# OBI_SlaveBoard_rev5.net
KiCad netlist of a schematic drawn in EAGLE
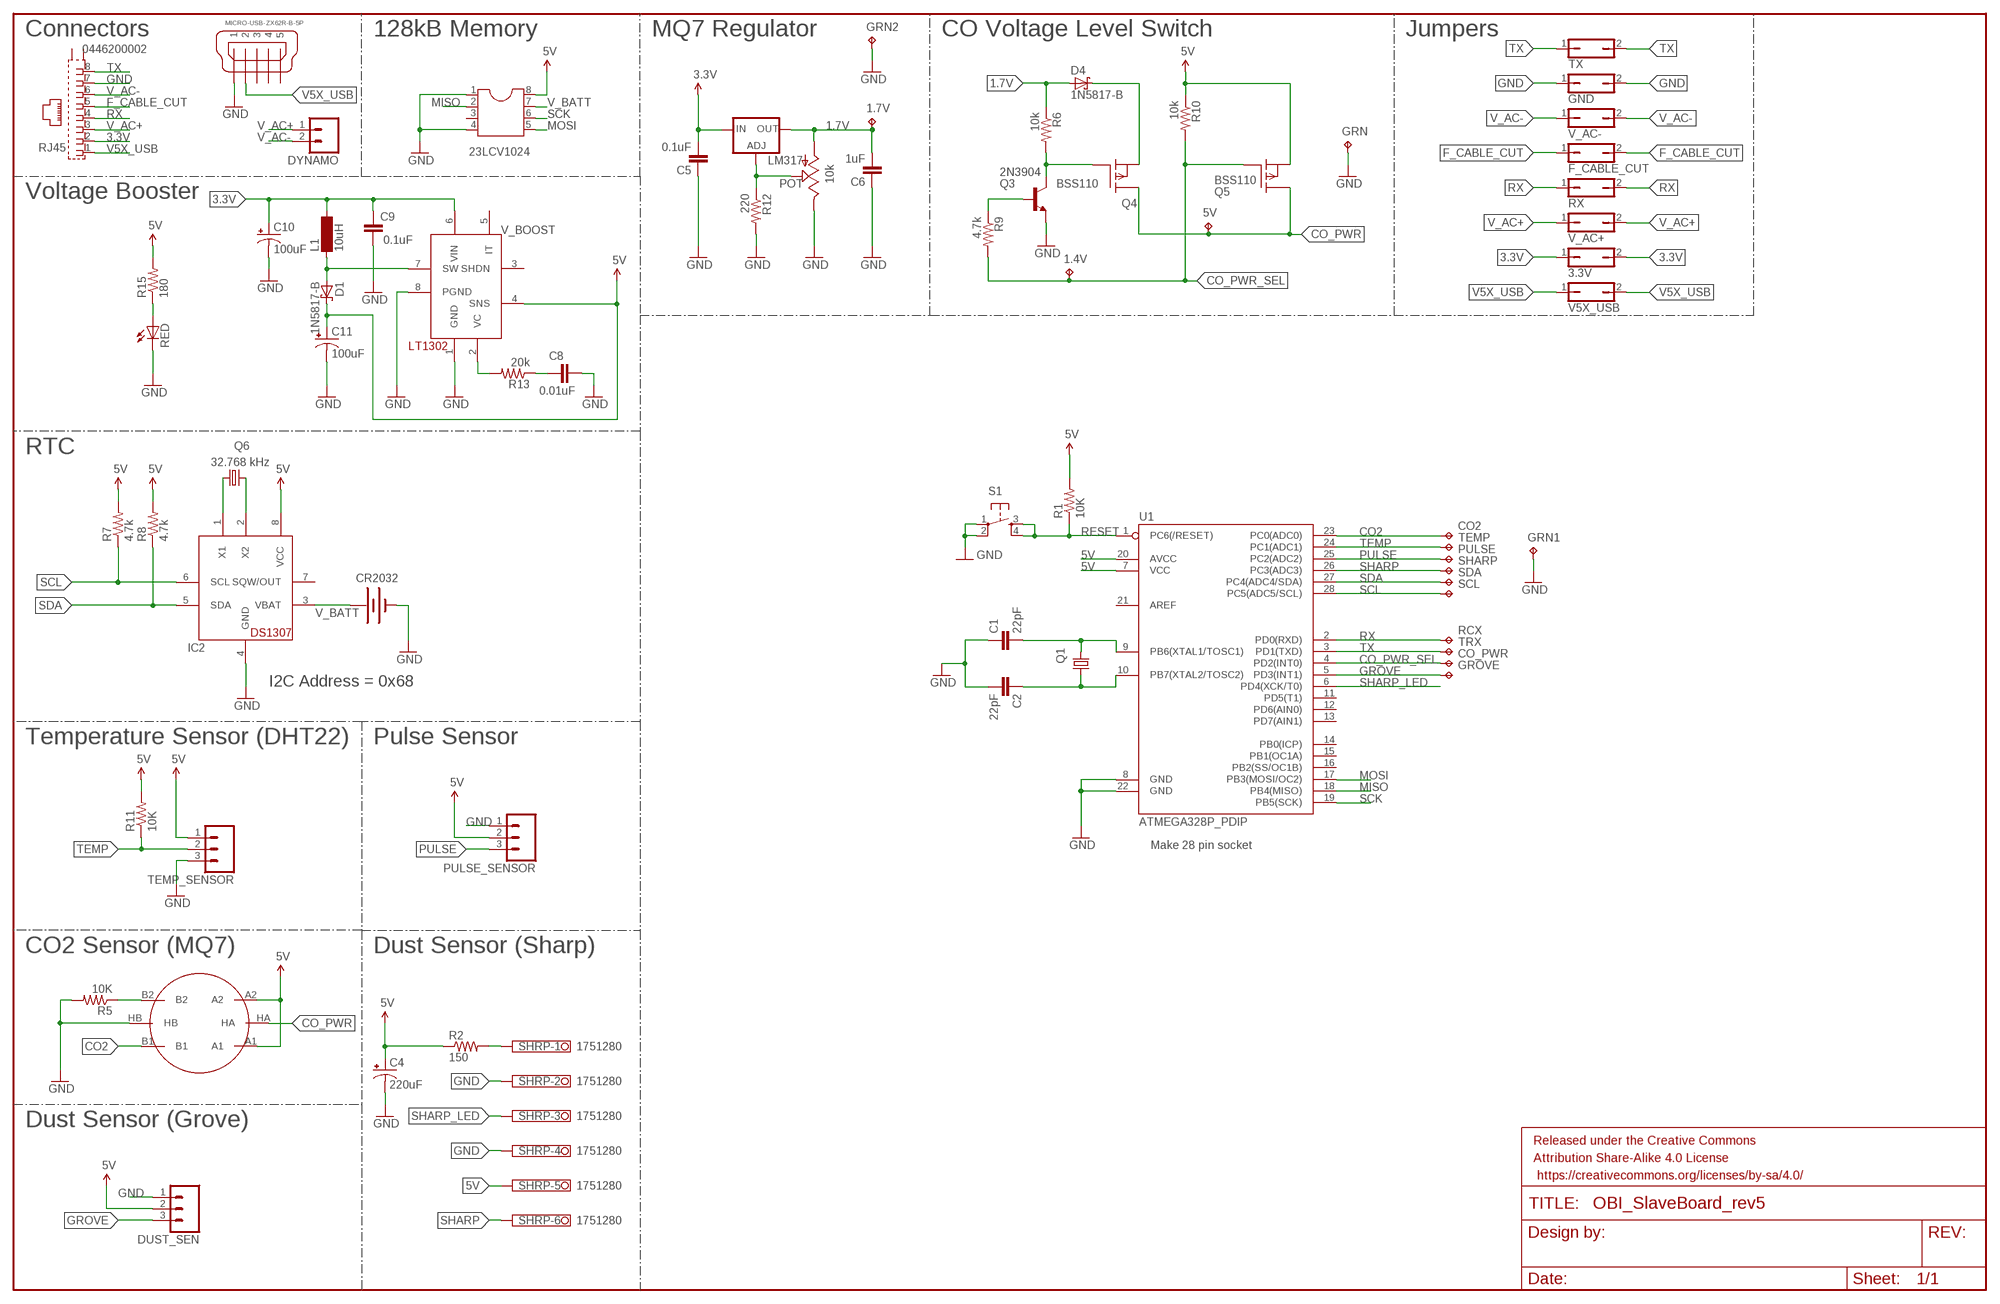
[diagram p0: schematic, sheet 1]

(export (version "E")
  (design (tool "Eeschema 10.0.6"))
  (components
    (comp (ref "1.4V")
      (value "TPPAD1-13")
      (footprint "eagle-import:P1-13")
      (libsource (lib "eagle-import") (part "TPPAD1-13"))
    )
    (comp (ref "1.7V")
      (value "TPPAD1-13")
      (footprint "eagle-import:P1-13")
      (libsource (lib "eagle-import") (part "TPPAD1-13"))
    )
    (comp (ref "3.3V")
      (value "JP1Q")
      (footprint "eagle-import:JP1")
      (libsource (lib "eagle-import") (part "JP1Q"))
    )
    (comp (ref "5V")
      (value "TPPAD1-13")
      (footprint "eagle-import:P1-13")
      (libsource (lib "eagle-import") (part "TPPAD1-13"))
    )
    (comp (ref "23LCV1024")
      (value "DIL8S")
      (footprint "eagle-import:SOCKET-08")
      (libsource (lib "eagle-import") (part "DIL8S"))
    )
    (comp (ref "C1")
      (value "22pF")
      (footprint "eagle-import:CAP-PTH-SMALL-KIT")
      (libsource (lib "eagle-import") (part "CAPKIT"))
    )
    (comp (ref "C2")
      (value "22pF")
      (footprint "eagle-import:CAP-PTH-SMALL-KIT")
      (libsource (lib "eagle-import") (part "CAPKIT"))
    )
    (comp (ref "C4")
      (value "220uF")
      (footprint "eagle-import:CPOL-RADIAL-10UF-25V")
      (libsource (lib "eagle-import") (part "CAP_POLPTH2"))
    )
    (comp (ref "C5")
      (value "0.1uF")
      (footprint "eagle-import:CAP-PTH-SMALL-KIT")
      (libsource (lib "eagle-import") (part "CAPKIT"))
    )
    (comp (ref "C6")
      (value "1uF")
      (footprint "eagle-import:CAP-PTH-SMALL-KIT")
      (libsource (lib "eagle-import") (part "CAPKIT"))
    )
    (comp (ref "C8")
      (value "0.01uF")
      (footprint "eagle-import:CAP-PTH-SMALL-KIT")
      (libsource (lib "eagle-import") (part "CAPKIT"))
    )
    (comp (ref "C9")
      (value "0.1uF")
      (footprint "eagle-import:CAP-PTH-SMALL-KIT")
      (libsource (lib "eagle-import") (part "CAPKIT"))
    )
    (comp (ref "C10")
      (value "100uF")
      (footprint "eagle-import:TT2D5")
      (libsource (lib "eagle-import") (part "CPOL-USTT2D5"))
    )
    (comp (ref "C11")
      (value "100uF")
      (footprint "eagle-import:TT2D5")
      (libsource (lib "eagle-import") (part "CPOL-USTT2D5"))
    )
    (comp (ref "CO2")
      (value "TPPAD1-13")
      (footprint "eagle-import:P1-13")
      (libsource (lib "eagle-import") (part "TPPAD1-13"))
    )
    (comp (ref "CO2_SENSOR")
      (value "METHANE_SENSOR")
      (footprint "eagle-import:MQ-3")
      (libsource (lib "eagle-import") (part "METHANE_SENSOR"))
    )
    (comp (ref "CO_PWR")
      (value "TPPAD1-13")
      (footprint "eagle-import:P1-13")
      (libsource (lib "eagle-import") (part "TPPAD1-13"))
    )
    (comp (ref "CR2032")
      (value "BATTERY20PTH")
      (footprint "eagle-import:BATTCOM_20MM_PTH")
      (libsource (lib "eagle-import") (part "BATTERY20PTH"))
    )
    (comp (ref "D1")
      (value "1N5817-B")
      (footprint "eagle-import:DO41-10")
      (libsource (lib "eagle-import") (part "SCHOTTKY-DIODEDO41"))
    )
    (comp (ref "D4")
      (value "1N5817-B")
      (footprint "eagle-import:DO41-10")
      (libsource (lib "eagle-import") (part "SCHOTTKY-DIODEDO41"))
    )
    (comp (ref "DUST_SEN")
      (value "M03SCREW")
      (footprint "eagle-import:SCREWTERMINAL-3.5MM-3")
      (libsource (lib "eagle-import") (part "M03SCREW"))
    )
    (comp (ref "DYNAMO")
      (value "M023.5MM")
      (footprint "eagle-import:SCREWTERMINAL-3.5MM-2")
      (libsource (lib "eagle-import") (part "M023.5MM"))
    )
    (comp (ref "FRAME1")
      (value "FRAME-LEDGER")
      (footprint "eagle-import:CREATIVE_COMMONS")
      (libsource (lib "eagle-import") (part "FRAME-LEDGER"))
    )
    (comp (ref "F_CABLE_CUT")
      (value "JP1Q")
      (footprint "eagle-import:JP1")
      (libsource (lib "eagle-import") (part "JP1Q"))
    )
    (comp (ref "GND")
      (value "JP1Q")
      (footprint "eagle-import:JP1")
      (libsource (lib "eagle-import") (part "JP1Q"))
    )
    (comp (ref "GRN")
      (value "TPPAD1-13")
      (footprint "eagle-import:P1-13")
      (libsource (lib "eagle-import") (part "TPPAD1-13"))
    )
    (comp (ref "GRN1")
      (value "TPPAD1-13")
      (footprint "eagle-import:P1-13")
      (libsource (lib "eagle-import") (part "TPPAD1-13"))
    )
    (comp (ref "GRN2")
      (value "TPPAD1-13")
      (footprint "eagle-import:P1-13")
      (libsource (lib "eagle-import") (part "TPPAD1-13"))
    )
    (comp (ref "GROVE")
      (value "TPPAD1-13")
      (footprint "eagle-import:P1-13")
      (libsource (lib "eagle-import") (part "TPPAD1-13"))
    )
    (comp (ref "IC2")
      (value "DS1307")
      (footprint "eagle-import:DIL08")
      (libsource (lib "eagle-import") (part "DS1307"))
    )
    (comp (ref "L1")
      (value "10uH")
      (footprint "eagle-import:BS11")
      (libsource (lib "eagle-import") (part "BS11"))
    )
    (comp (ref "LM317")
      (value "LM317TS")
      (footprint "eagle-import:317TS")
      (libsource (lib "eagle-import") (part "LM317TS"))
    )
    (comp (ref "MICROB")
      (value "MICRO-USB-ZX62R-B-5P")
      (footprint "eagle-import:ZX62R-B-5P")
      (libsource (lib "eagle-import") (part "MICRO-USB-ZX62R-B-5P"))
    )
    (comp (ref "POT")
      (value "10k")
      (footprint "eagle-import:CT6")
      (libsource (lib "eagle-import") (part "TRIM_US-CT6"))
    )
    (comp (ref "PULSE")
      (value "TPPAD1-13")
      (footprint "eagle-import:P1-13")
      (libsource (lib "eagle-import") (part "TPPAD1-13"))
    )
    (comp (ref "PULSE_SENSOR")
      (value "M03SCREW")
      (footprint "eagle-import:SCREWTERMINAL-3.5MM-3")
      (libsource (lib "eagle-import") (part "M03SCREW"))
    )
    (comp (ref "Q1")
      (value "CRYSTALHC49S")
      (footprint "eagle-import:HC49_S")
      (libsource (lib "eagle-import") (part "CRYSTALHC49S"))
    )
    (comp (ref "Q3")
      (value "2N3904")
      (footprint "eagle-import:TO-92")
      (libsource (lib "eagle-import") (part "TRANSISTOR_NPN2N3904"))
    )
    (comp (ref "Q4")
      (value "BSS110")
      (footprint "eagle-import:TO92")
      (libsource (lib "eagle-import") (part "BSS110"))
    )
    (comp (ref "Q5")
      (value "BSS110")
      (footprint "eagle-import:TO92")
      (libsource (lib "eagle-import") (part "BSS110"))
    )
    (comp (ref "Q6")
      (value "32.768 kHz")
      (footprint "eagle-import:TC26V")
      (libsource (lib "eagle-import") (part "CRYSTALTC26V"))
    )
    (comp (ref "R1")
      (value "10K")
      (footprint "eagle-import:AXIAL-0.4")
      (libsource (lib "eagle-import") (part "RESISTORPTH-1/4W"))
    )
    (comp (ref "R2")
      (value "150")
      (footprint "eagle-import:AXIAL-0.4")
      (libsource (lib "eagle-import") (part "SparkFun-Resistors_RESISTORPTH-1/4W"))
    )
    (comp (ref "R5")
      (value "10K")
      (footprint "eagle-import:AXIAL-0.4")
      (libsource (lib "eagle-import") (part "RESISTORPTH-1/4W"))
    )
    (comp (ref "R6")
      (value "10k")
      (footprint "eagle-import:AXIAL-0.4")
      (libsource (lib "eagle-import") (part "SparkFun-Resistors_RESISTORPTH-1/4W"))
    )
    (comp (ref "R7")
      (value "4.7k")
      (footprint "eagle-import:AXIAL-0.4")
      (libsource (lib "eagle-import") (part "RESISTORPTH-1/4W"))
    )
    (comp (ref "R8")
      (value "4.7k")
      (footprint "eagle-import:AXIAL-0.4")
      (libsource (lib "eagle-import") (part "RESISTORPTH-1/4W"))
    )
    (comp (ref "R9")
      (value "4.7k")
      (footprint "eagle-import:AXIAL-0.4")
      (libsource (lib "eagle-import") (part "SparkFun-Resistors_RESISTORPTH-1/4W"))
    )
    (comp (ref "R10")
      (value "10k")
      (footprint "eagle-import:AXIAL-0.4")
      (libsource (lib "eagle-import") (part "SparkFun-Resistors_RESISTORPTH-1/4W"))
    )
    (comp (ref "R11")
      (value "10K")
      (footprint "eagle-import:AXIAL-0.4")
      (libsource (lib "eagle-import") (part "SparkFun-Resistors_RESISTORPTH-1/4W"))
    )
    (comp (ref "R12")
      (value "220")
      (footprint "eagle-import:AXIAL-0.4")
      (libsource (lib "eagle-import") (part "SparkFun-Resistors_RESISTORPTH-1/4W"))
    )
    (comp (ref "R13")
      (value "20k")
      (footprint "eagle-import:AXIAL-0.4")
      (libsource (lib "eagle-import") (part "SparkFun-Resistors_RESISTORPTH-1/4W"))
    )
    (comp (ref "R15")
      (value "180")
      (footprint "eagle-import:AXIAL-0.4")
      (libsource (lib "eagle-import") (part "RESISTORPTH-1/4W"))
    )
    (comp (ref "RCX")
      (value "TPPAD1-13")
      (footprint "eagle-import:P1-13")
      (libsource (lib "eagle-import") (part "TPPAD1-13"))
    )
    (comp (ref "RED")
      (value "LEDCHIPLED_1206")
      (footprint "eagle-import:CHIPLED_1206")
      (libsource (lib "eagle-import") (part "LEDCHIPLED_1206"))
    )
    (comp (ref "RJ45")
      (value "0446200002")
      (footprint "eagle-import:0446200002")
      (fields (field (name "MF") "MOLEX"))
      (libsource (lib "eagle-import") (part "0446200002"))
    )
    (comp (ref "RX")
      (value "JP1Q")
      (footprint "eagle-import:JP1")
      (libsource (lib "eagle-import") (part "JP1Q"))
    )
    (comp (ref "S1")
      (value "TAC_SWITCHPTH")
      (footprint "eagle-import:TACTILE-PTH")
      (libsource (lib "eagle-import") (part "TAC_SWITCHPTH"))
    )
    (comp (ref "SCL")
      (value "TPPAD1-13")
      (footprint "eagle-import:P1-13")
      (libsource (lib "eagle-import") (part "TPPAD1-13"))
    )
    (comp (ref "SDA")
      (value "TPPAD1-13")
      (footprint "eagle-import:P1-13")
      (libsource (lib "eagle-import") (part "TPPAD1-13"))
    )
    (comp (ref "SHARP")
      (value "TPPAD1-13")
      (footprint "eagle-import:P1-13")
      (libsource (lib "eagle-import") (part "TPPAD1-13"))
    )
    (comp (ref "SHRP")
      (value "1751280")
      (footprint "eagle-import:1751280")
      (libsource (lib "eagle-import") (part "1751280"))
    )
    (comp (ref "TEMP")
      (value "TPPAD1-13")
      (footprint "eagle-import:P1-13")
      (libsource (lib "eagle-import") (part "TPPAD1-13"))
    )
    (comp (ref "TEMP_SENSOR")
      (value "M03SCREW")
      (footprint "eagle-import:SCREWTERMINAL-3.5MM-3")
      (libsource (lib "eagle-import") (part "M03SCREW"))
    )
    (comp (ref "TRX")
      (value "TPPAD1-13")
      (footprint "eagle-import:P1-13")
      (libsource (lib "eagle-import") (part "TPPAD1-13"))
    )
    (comp (ref "TX")
      (value "JP1Q")
      (footprint "eagle-import:JP1")
      (libsource (lib "eagle-import") (part "JP1Q"))
    )
    (comp (ref "U1")
      (value "ATMEGA328P_PDIP")
      (footprint "eagle-import:DIL28-3")
      (libsource (lib "eagle-import") (part "ATMEGA328P_PDIP"))
    )
    (comp (ref "V5X_USB")
      (value "JP1Q")
      (footprint "eagle-import:JP1")
      (libsource (lib "eagle-import") (part "JP1Q"))
    )
    (comp (ref "V_AC+")
      (value "JP1Q")
      (footprint "eagle-import:JP1")
      (libsource (lib "eagle-import") (part "JP1Q"))
    )
    (comp (ref "V_AC-")
      (value "JP1Q")
      (footprint "eagle-import:JP1")
      (libsource (lib "eagle-import") (part "JP1Q"))
    )
    (comp (ref "V_BOOST")
      (value "LT1302")
      (footprint "eagle-import:DIL08")
      (libsource (lib "eagle-import") (part "LT1302"))
    )
  )
  (nets
    (net (code "1") (name "/MISO") (class "Default")
      (node (ref "23LCV1024") (pin "2") (pinfunction "2_2") (pintype "passive"))
      (node (ref "U1") (pin "18") (pinfunction "PB4(MISO)_18") (pintype "bidirectional"))
    )
    (net (code "2") (name "/MOSI") (class "Default")
      (node (ref "23LCV1024") (pin "5") (pinfunction "5_5") (pintype "passive"))
      (node (ref "U1") (pin "17") (pinfunction "PB3(MOSI/OC2)_17") (pintype "bidirectional"))
    )
    (net (code "3") (name "/RESET") (class "Default")
      (node (ref "R1") (pin "P$1") (pinfunction "1_P$1") (pintype "passive"))
      (node (ref "S1") (pin "3") (pinfunction "3_3") (pintype "passive"))
      (node (ref "S1") (pin "4") (pinfunction "4_4") (pintype "passive"))
      (node (ref "U1") (pin "1") (pinfunction "PC6(/RESET)_1") (pintype "bidirectional"))
    )
    (net (code "4") (name "/SCK") (class "Default")
      (node (ref "23LCV1024") (pin "6") (pinfunction "6_6") (pintype "passive"))
      (node (ref "U1") (pin "19") (pinfunction "PB5(SCK)_19") (pintype "bidirectional"))
    )
    (net (code "5") (name "/V_BATT") (class "Default")
      (node (ref "23LCV1024") (pin "7") (pinfunction "7_7") (pintype "passive"))
      (node (ref "CR2032") (pin "1") (pinfunction "+_1") (pintype "power_in"))
      (node (ref "IC2") (pin "3") (pinfunction "VBAT_3") (pintype "power_in"))
    )
    (net (code "6") (name "1.7V") (class "Default")
      (node (ref "1.7V") (pin "TP") (pinfunction "TP_TP") (pintype "input"))
      (node (ref "C6") (pin "2") (pinfunction "2_2") (pintype "passive"))
      (node (ref "D4") (pin "A") (pinfunction "A_A") (pintype "passive"))
      (node (ref "LM317") (pin "2") (pinfunction "OUT_2") (pintype "passive"))
      (node (ref "POT") (pin "A") (pinfunction "A_A") (pintype "passive"))
      (node (ref "R6") (pin "P$1") (pinfunction "1_P$1") (pintype "passive"))
    )
    (net (code "7") (name "3.3V") (class "Default")
      (node (ref "3.3V") (pin "1") (pinfunction "1_1") (pintype "passive"))
      (node (ref "3.3V") (pin "2") (pinfunction "2_2") (pintype "passive"))
      (node (ref "C10") (pin "+") (pinfunction "+_+") (pintype "passive"))
      (node (ref "C5") (pin "2") (pinfunction "2_2") (pintype "passive"))
      (node (ref "C9") (pin "1") (pinfunction "1_1") (pintype "passive"))
      (node (ref "L1") (pin "2") (pinfunction "2_2") (pintype "passive"))
      (node (ref "LM317") (pin "3") (pinfunction "IN_3") (pintype "input"))
      (node (ref "RJ45") (pin "2") (pinfunction "2_2") (pintype "passive"))
      (node (ref "V_BOOST") (pin "6") (pinfunction "VIN_6") (pintype "input"))
    )
    (net (code "8") (name "5V") (class "Default")
      (node (ref "23LCV1024") (pin "8") (pinfunction "8_8") (pintype "passive"))
      (node (ref "C11") (pin "+") (pinfunction "+_+") (pintype "passive"))
      (node (ref "C4") (pin "1") (pinfunction "+_1") (pintype "passive"))
      (node (ref "CO2_SENSOR") (pin "A1") (pinfunction "A1_A1") (pintype "bidirectional"))
      (node (ref "CO2_SENSOR") (pin "A2") (pinfunction "A2_A2") (pintype "bidirectional"))
      (node (ref "D1") (pin "C") (pinfunction "C_C") (pintype "passive"))
      (node (ref "DUST_SEN") (pin "2") (pinfunction "2_2") (pintype "passive"))
      (node (ref "IC2") (pin "8") (pinfunction "VCC_8") (pintype "power_in"))
      (node (ref "PULSE_SENSOR") (pin "2") (pinfunction "2_2") (pintype "passive"))
      (node (ref "Q5") (pin "1") (pinfunction "S_1") (pintype "passive"))
      (node (ref "R1") (pin "P$2") (pinfunction "2_P$2") (pintype "passive"))
      (node (ref "R10") (pin "P$1") (pinfunction "1_P$1") (pintype "passive"))
      (node (ref "R11") (pin "P$2") (pinfunction "2_P$2") (pintype "passive"))
      (node (ref "R15") (pin "P$2") (pinfunction "2_P$2") (pintype "passive"))
      (node (ref "R2") (pin "P$1") (pinfunction "1_P$1") (pintype "passive"))
      (node (ref "R7") (pin "P$2") (pinfunction "2_P$2") (pintype "passive"))
      (node (ref "R8") (pin "P$2") (pinfunction "2_P$2") (pintype "passive"))
      (node (ref "SHRP") (pin "5") (pinfunction "K_5") (pintype "passive"))
      (node (ref "TEMP_SENSOR") (pin "1") (pinfunction "1_1") (pintype "passive"))
      (node (ref "U1") (pin "20") (pinfunction "AVCC_20") (pintype "bidirectional"))
      (node (ref "U1") (pin "7") (pinfunction "VCC_7") (pintype "bidirectional"))
      (node (ref "V_BOOST") (pin "4") (pinfunction "SNS_4") (pintype "passive"))
    )
    (net (code "9") (name "CO2") (class "Default")
      (node (ref "CO2") (pin "TP") (pinfunction "TP_TP") (pintype "input"))
      (node (ref "CO2_SENSOR") (pin "B1") (pinfunction "B1_B1") (pintype "bidirectional"))
      (node (ref "U1") (pin "23") (pinfunction "PC0(ADC0)_23") (pintype "bidirectional"))
    )
    (net (code "10") (name "CO_PWR") (class "Default")
      (node (ref "5V") (pin "TP") (pinfunction "TP_TP") (pintype "input"))
      (node (ref "CO2_SENSOR") (pin "HA") (pinfunction "HA_HA") (pintype "bidirectional"))
      (node (ref "Q4") (pin "3") (pinfunction "D_3") (pintype "passive"))
      (node (ref "Q5") (pin "3") (pinfunction "D_3") (pintype "passive"))
    )
    (net (code "11") (name "CO_PWR_SEL") (class "Default")
      (node (ref "1.4V") (pin "TP") (pinfunction "TP_TP") (pintype "input"))
      (node (ref "CO_PWR") (pin "TP") (pinfunction "TP_TP") (pintype "input"))
      (node (ref "Q5") (pin "2") (pinfunction "G_2") (pintype "passive"))
      (node (ref "R10") (pin "P$2") (pinfunction "2_P$2") (pintype "passive"))
      (node (ref "R9") (pin "P$2") (pinfunction "2_P$2") (pintype "passive"))
      (node (ref "U1") (pin "4") (pinfunction "PD2(INT0)_4") (pintype "bidirectional"))
    )
    (net (code "12") (name "F_CABLE_CUT") (class "Default")
      (node (ref "F_CABLE_CUT") (pin "1") (pinfunction "1_1") (pintype "passive"))
      (node (ref "F_CABLE_CUT") (pin "2") (pinfunction "2_2") (pintype "passive"))
      (node (ref "RJ45") (pin "5") (pinfunction "5_5") (pintype "passive"))
    )
    (net (code "13") (name "GND") (class "Default")
      (node (ref "23LCV1024") (pin "1") (pinfunction "1_1") (pintype "passive"))
      (node (ref "23LCV1024") (pin "4") (pinfunction "4_4") (pintype "passive"))
      (node (ref "C1") (pin "1") (pinfunction "1_1") (pintype "passive"))
      (node (ref "C10") (pin "-") (pinfunction "-_-") (pintype "passive"))
      (node (ref "C11") (pin "-") (pinfunction "-_-") (pintype "passive"))
      (node (ref "C2") (pin "2") (pinfunction "2_2") (pintype "passive"))
      (node (ref "C4") (pin "2") (pinfunction "-_2") (pintype "passive"))
      (node (ref "C5") (pin "1") (pinfunction "1_1") (pintype "passive"))
      (node (ref "C6") (pin "1") (pinfunction "1_1") (pintype "passive"))
      (node (ref "C8") (pin "1") (pinfunction "1_1") (pintype "passive"))
      (node (ref "C9") (pin "2") (pinfunction "2_2") (pintype "passive"))
      (node (ref "CO2_SENSOR") (pin "HB") (pinfunction "HB_HB") (pintype "bidirectional"))
      (node (ref "CR2032") (pin "2") (pinfunction "-_2") (pintype "power_in"))
      (node (ref "DUST_SEN") (pin "1") (pinfunction "1_1") (pintype "passive"))
      (node (ref "GND") (pin "1") (pinfunction "1_1") (pintype "passive"))
      (node (ref "GND") (pin "2") (pinfunction "2_2") (pintype "passive"))
      (node (ref "GRN") (pin "TP") (pinfunction "TP_TP") (pintype "input"))
      (node (ref "GRN1") (pin "TP") (pinfunction "TP_TP") (pintype "input"))
      (node (ref "GRN2") (pin "TP") (pinfunction "TP_TP") (pintype "input"))
      (node (ref "IC2") (pin "4") (pinfunction "GND_4") (pintype "power_in"))
      (node (ref "MICROB") (pin "1") (pinfunction "1_1") (pintype "input"))
      (node (ref "POT") (pin "E") (pinfunction "E_E") (pintype "passive"))
      (node (ref "PULSE_SENSOR") (pin "1") (pinfunction "1_1") (pintype "passive"))
      (node (ref "Q3") (pin "1") (pinfunction "E_1") (pintype "passive"))
      (node (ref "R12") (pin "P$2") (pinfunction "2_P$2") (pintype "passive"))
      (node (ref "R5") (pin "P$2") (pinfunction "2_P$2") (pintype "passive"))
      (node (ref "RED") (pin "C") (pinfunction "C_C") (pintype "passive"))
      (node (ref "RJ45") (pin "7") (pinfunction "7_7") (pintype "passive"))
      (node (ref "S1") (pin "1") (pinfunction "1_1") (pintype "passive"))
      (node (ref "S1") (pin "2") (pinfunction "2_2") (pintype "passive"))
      (node (ref "SHRP") (pin "2") (pinfunction "K_2") (pintype "passive"))
      (node (ref "SHRP") (pin "4") (pinfunction "K_4") (pintype "passive"))
      (node (ref "TEMP_SENSOR") (pin "3") (pinfunction "3_3") (pintype "passive"))
      (node (ref "U1") (pin "22") (pinfunction "GND_22") (pintype "bidirectional"))
      (node (ref "U1") (pin "8") (pinfunction "GND_8") (pintype "bidirectional"))
      (node (ref "V_BOOST") (pin "1") (pinfunction "GND_1") (pintype "input"))
      (node (ref "V_BOOST") (pin "8") (pinfunction "PGND_8") (pintype "input"))
    )
    (net (code "14") (name "GROVE") (class "Default")
      (node (ref "DUST_SEN") (pin "3") (pinfunction "3_3") (pintype "passive"))
      (node (ref "GROVE") (pin "TP") (pinfunction "TP_TP") (pintype "input"))
      (node (ref "U1") (pin "5") (pinfunction "PD3(INT1)_5") (pintype "bidirectional"))
    )
    (net (code "15") (name "Net-(IC2-X1)") (class "Default")
      (node (ref "IC2") (pin "1") (pinfunction "X1_1") (pintype "passive"))
      (node (ref "Q6") (pin "1") (pinfunction "1_1") (pintype "passive"))
    )
    (net (code "16") (name "Net-(IC2-X2)") (class "Default")
      (node (ref "IC2") (pin "2") (pinfunction "X2_2") (pintype "passive"))
      (node (ref "Q6") (pin "2") (pinfunction "2_2") (pintype "passive"))
    )
    (net (code "17") (name "Net-(LM317-ADJ)") (class "Default")
      (node (ref "LM317") (pin "1") (pinfunction "ADJ_1") (pintype "input"))
      (node (ref "POT") (pin "S") (pinfunction "S_S") (pintype "passive"))
      (node (ref "R12") (pin "P$1") (pinfunction "1_P$1") (pintype "passive"))
    )
    (net (code "18") (name "Net-(Q3-B)") (class "Default")
      (node (ref "Q3") (pin "2") (pinfunction "B_2") (pintype "passive"))
      (node (ref "R9") (pin "P$1") (pinfunction "1_P$1") (pintype "passive"))
    )
    (net (code "19") (name "Net-(Q3-C)") (class "Default")
      (node (ref "Q3") (pin "3") (pinfunction "C_3") (pintype "passive"))
      (node (ref "Q4") (pin "2") (pinfunction "G_2") (pintype "passive"))
      (node (ref "R6") (pin "P$2") (pinfunction "2_P$2") (pintype "passive"))
    )
    (net (code "20") (name "Net-(Q4-S)") (class "Default")
      (node (ref "D4") (pin "C") (pinfunction "C_C") (pintype "passive"))
      (node (ref "Q4") (pin "1") (pinfunction "S_1") (pintype "passive"))
    )
    (net (code "21") (name "Net-(R2-2)") (class "Default")
      (node (ref "R2") (pin "P$2") (pinfunction "2_P$2") (pintype "passive"))
      (node (ref "SHRP") (pin "1") (pinfunction "K_1") (pintype "passive"))
    )
    (net (code "22") (name "Net-(R5-1)") (class "Default")
      (node (ref "CO2_SENSOR") (pin "B2") (pinfunction "B2_B2") (pintype "bidirectional"))
      (node (ref "R5") (pin "P$1") (pinfunction "1_P$1") (pintype "passive"))
    )
    (net (code "23") (name "Net-(R13-1)") (class "Default")
      (node (ref "C8") (pin "2") (pinfunction "2_2") (pintype "passive"))
      (node (ref "R13") (pin "P$1") (pinfunction "1_P$1") (pintype "passive"))
    )
    (net (code "24") (name "Net-(R13-2)") (class "Default")
      (node (ref "R13") (pin "P$2") (pinfunction "2_P$2") (pintype "passive"))
      (node (ref "V_BOOST") (pin "2") (pinfunction "VC_2") (pintype "passive"))
    )
    (net (code "25") (name "Net-(R15-1)") (class "Default")
      (node (ref "R15") (pin "P$1") (pinfunction "1_P$1") (pintype "passive"))
      (node (ref "RED") (pin "A") (pinfunction "A_A") (pintype "passive"))
    )
    (net (code "26") (name "Net-(U1-PB6(XTAL1{slash}TOSC1))") (class "Default")
      (node (ref "C1") (pin "2") (pinfunction "2_2") (pintype "passive"))
      (node (ref "Q1") (pin "2") (pinfunction "2_2") (pintype "passive"))
      (node (ref "U1") (pin "9") (pinfunction "PB6(XTAL1/TOSC1)_9") (pintype "bidirectional"))
    )
    (net (code "27") (name "Net-(U1-PB7(XTAL2{slash}TOSC2))") (class "Default")
      (node (ref "C2") (pin "1") (pinfunction "1_1") (pintype "passive"))
      (node (ref "Q1") (pin "1") (pinfunction "1_1") (pintype "passive"))
      (node (ref "U1") (pin "10") (pinfunction "PB7(XTAL2/TOSC2)_10") (pintype "bidirectional"))
    )
    (net (code "28") (name "Net-(V_BOOST-SW)") (class "Default")
      (node (ref "D1") (pin "A") (pinfunction "A_A") (pintype "passive"))
      (node (ref "L1") (pin "1") (pinfunction "1_1") (pintype "passive"))
      (node (ref "V_BOOST") (pin "7") (pinfunction "SW_7") (pintype "input"))
    )
    (net (code "29") (name "PULSE") (class "Default")
      (node (ref "PULSE") (pin "TP") (pinfunction "TP_TP") (pintype "input"))
      (node (ref "PULSE_SENSOR") (pin "3") (pinfunction "3_3") (pintype "passive"))
      (node (ref "U1") (pin "25") (pinfunction "PC2(ADC2)_25") (pintype "bidirectional"))
    )
    (net (code "30") (name "RX") (class "Default")
      (node (ref "RCX") (pin "TP") (pinfunction "TP_TP") (pintype "input"))
      (node (ref "RJ45") (pin "4") (pinfunction "4_4") (pintype "passive"))
      (node (ref "RX") (pin "1") (pinfunction "1_1") (pintype "passive"))
      (node (ref "RX") (pin "2") (pinfunction "2_2") (pintype "passive"))
      (node (ref "U1") (pin "2") (pinfunction "PD0(RXD)_2") (pintype "bidirectional"))
    )
    (net (code "31") (name "SCL") (class "Default")
      (node (ref "IC2") (pin "6") (pinfunction "SCL_6") (pintype "bidirectional"))
      (node (ref "R7") (pin "P$1") (pinfunction "1_P$1") (pintype "passive"))
      (node (ref "SCL") (pin "TP") (pinfunction "TP_TP") (pintype "input"))
      (node (ref "U1") (pin "28") (pinfunction "PC5(ADC5/SCL)_28") (pintype "bidirectional"))
    )
    (net (code "32") (name "SDA") (class "Default")
      (node (ref "IC2") (pin "5") (pinfunction "SDA_5") (pintype "bidirectional"))
      (node (ref "R8") (pin "P$1") (pinfunction "1_P$1") (pintype "passive"))
      (node (ref "SDA") (pin "TP") (pinfunction "TP_TP") (pintype "input"))
      (node (ref "U1") (pin "27") (pinfunction "PC4(ADC4/SDA)_27") (pintype "bidirectional"))
    )
    (net (code "33") (name "SHARP") (class "Default")
      (node (ref "SHARP") (pin "TP") (pinfunction "TP_TP") (pintype "input"))
      (node (ref "SHRP") (pin "6") (pinfunction "K_6") (pintype "passive"))
      (node (ref "U1") (pin "26") (pinfunction "PC3(ADC3)_26") (pintype "bidirectional"))
    )
    (net (code "34") (name "SHARP_LED") (class "Default")
      (node (ref "SHRP") (pin "3") (pinfunction "K_3") (pintype "passive"))
      (node (ref "U1") (pin "6") (pinfunction "PD4(XCK/T0)_6") (pintype "bidirectional"))
    )
    (net (code "35") (name "TEMP") (class "Default")
      (node (ref "R11") (pin "P$1") (pinfunction "1_P$1") (pintype "passive"))
      (node (ref "TEMP") (pin "TP") (pinfunction "TP_TP") (pintype "input"))
      (node (ref "TEMP_SENSOR") (pin "2") (pinfunction "2_2") (pintype "passive"))
      (node (ref "U1") (pin "24") (pinfunction "PC1(ADC1)_24") (pintype "bidirectional"))
    )
    (net (code "36") (name "TX") (class "Default")
      (node (ref "RJ45") (pin "8") (pinfunction "8_8") (pintype "passive"))
      (node (ref "TRX") (pin "TP") (pinfunction "TP_TP") (pintype "input"))
      (node (ref "TX") (pin "1") (pinfunction "1_1") (pintype "passive"))
      (node (ref "TX") (pin "2") (pinfunction "2_2") (pintype "passive"))
      (node (ref "U1") (pin "3") (pinfunction "PD1(TXD)_3") (pintype "bidirectional"))
    )
    (net (code "37") (name "V5X_USB") (class "Default")
      (node (ref "MICROB") (pin "2") (pinfunction "2_2") (pintype "input"))
      (node (ref "RJ45") (pin "1") (pinfunction "1_1") (pintype "passive"))
      (node (ref "V5X_USB") (pin "1") (pinfunction "1_1") (pintype "passive"))
      (node (ref "V5X_USB") (pin "2") (pinfunction "2_2") (pintype "passive"))
    )
    (net (code "38") (name "V_AC+") (class "Default")
      (node (ref "DYNAMO") (pin "1") (pinfunction "1_1") (pintype "passive"))
      (node (ref "RJ45") (pin "3") (pinfunction "3_3") (pintype "passive"))
      (node (ref "V_AC+") (pin "1") (pinfunction "1_1") (pintype "passive"))
      (node (ref "V_AC+") (pin "2") (pinfunction "2_2") (pintype "passive"))
    )
    (net (code "39") (name "V_AC-") (class "Default")
      (node (ref "DYNAMO") (pin "2") (pinfunction "2_2") (pintype "passive"))
      (node (ref "RJ45") (pin "6") (pinfunction "6_6") (pintype "passive"))
      (node (ref "V_AC-") (pin "1") (pinfunction "1_1") (pintype "passive"))
      (node (ref "V_AC-") (pin "2") (pinfunction "2_2") (pintype "passive"))
    )
    (net (code "40") (name "unconnected-(23LCV1024-Pad3)") (class "Default")
      (node (ref "23LCV1024") (pin "3") (pinfunction "3_3") (pintype "passive"))
    )
    (net (code "41") (name "unconnected-(IC2-SQW{slash}OUT-Pad7)") (class "Default")
      (node (ref "IC2") (pin "7") (pinfunction "SQW/OUT_7") (pintype "bidirectional"))
    )
    (net (code "42") (name "unconnected-(MICROB-Pad3)") (class "Default")
      (node (ref "MICROB") (pin "3") (pinfunction "3_3") (pintype "input"))
    )
    (net (code "43") (name "unconnected-(MICROB-Pad4)") (class "Default")
      (node (ref "MICROB") (pin "4") (pinfunction "4_4") (pintype "input"))
    )
    (net (code "44") (name "unconnected-(MICROB-Pad5)") (class "Default")
      (node (ref "MICROB") (pin "5") (pinfunction "5_5") (pintype "input"))
    )
    (net (code "45") (name "unconnected-(RJ45-S1-PadS@1)") (class "Default")
      (node (ref "RJ45") (pin "S@1") (pinfunction "S1_S@1") (pintype "passive"))
    )
    (net (code "46") (name "unconnected-(RJ45-S2-PadS@2)") (class "Default")
      (node (ref "RJ45") (pin "S@2") (pinfunction "S2_S@2") (pintype "passive"))
    )
    (net (code "47") (name "unconnected-(U1-AREF-Pad21)") (class "Default")
      (node (ref "U1") (pin "21") (pinfunction "AREF_21") (pintype "bidirectional"))
    )
    (net (code "48") (name "unconnected-(U1-PB0(ICP)-Pad14)") (class "Default")
      (node (ref "U1") (pin "14") (pinfunction "PB0(ICP)_14") (pintype "bidirectional"))
    )
    (net (code "49") (name "unconnected-(U1-PB1(OC1A)-Pad15)") (class "Default")
      (node (ref "U1") (pin "15") (pinfunction "PB1(OC1A)_15") (pintype "bidirectional"))
    )
    (net (code "50") (name "unconnected-(U1-PB2(SS{slash}OC1B)-Pad16)") (class "Default")
      (node (ref "U1") (pin "16") (pinfunction "PB2(SS/OC1B)_16") (pintype "bidirectional"))
    )
    (net (code "51") (name "unconnected-(U1-PD5(T1)-Pad11)") (class "Default")
      (node (ref "U1") (pin "11") (pinfunction "PD5(T1)_11") (pintype "bidirectional"))
    )
    (net (code "52") (name "unconnected-(U1-PD6(AIN0)-Pad12)") (class "Default")
      (node (ref "U1") (pin "12") (pinfunction "PD6(AIN0)_12") (pintype "bidirectional"))
    )
    (net (code "53") (name "unconnected-(U1-PD7(AIN1)-Pad13)") (class "Default")
      (node (ref "U1") (pin "13") (pinfunction "PD7(AIN1)_13") (pintype "bidirectional"))
    )
    (net (code "54") (name "unconnected-(V_BOOST-IT-Pad5)") (class "Default")
      (node (ref "V_BOOST") (pin "5") (pinfunction "IT_5") (pintype "input"))
    )
    (net (code "55") (name "unconnected-(V_BOOST-SHDN-Pad3)") (class "Default")
      (node (ref "V_BOOST") (pin "3") (pinfunction "SHDN_3") (pintype "input"))
    )
  )
)
